# GPIOSheet.net
KiCad netlist of a schematic drawn in Altium Designer
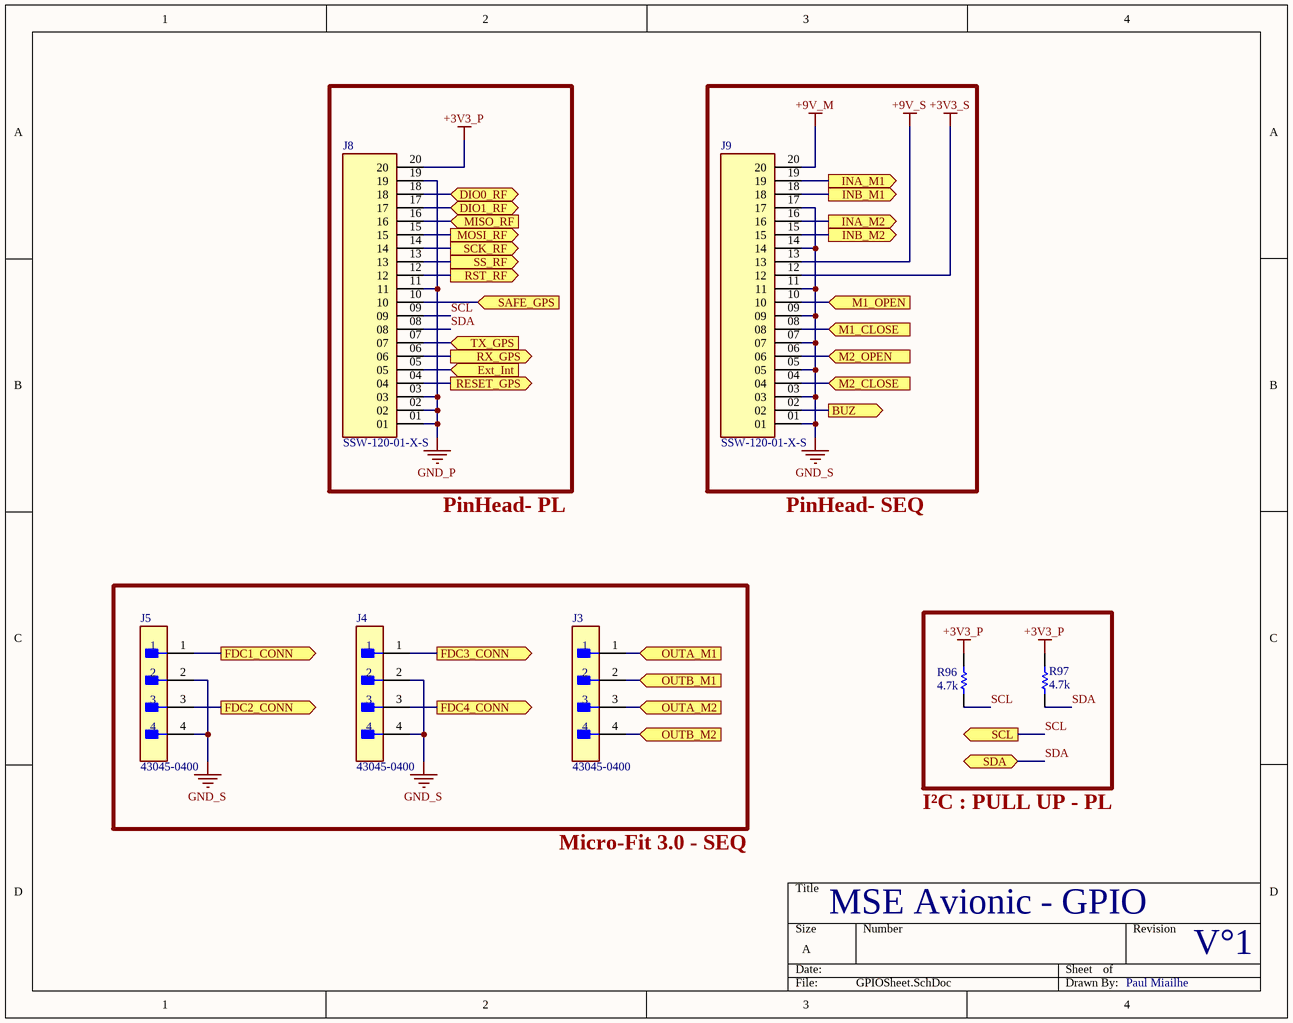
[diagram p0: GPIOSheet.SchDoc]

(export (version "E")
  (design (tool "Eeschema 10.0.6"))
  (components
    (comp (ref "J3")
      (value "43045-0400")
      (footprint "FP-43045-0400-MFG")
      (description "CONN HEADER R/A 4POS 3MM")
      (fields
        (field (name "MANUFACTURER") "Molex")
        (field (name "OCTOPART") "https://octopart.com/43045-0400-molex-287063")
      )
      (libsource (lib "Altium Content Vault") (part "c01754ab0efc13afb7424b896f394ef"))
    )
    (comp (ref "J4")
      (value "43045-0400")
      (footprint "FP-43045-0400-MFG")
      (description "CONN HEADER R/A 4POS 3MM")
      (fields
        (field (name "MANUFACTURER") "Molex")
        (field (name "OCTOPART") "https://octopart.com/43045-0400-molex-287063")
      )
      (libsource (lib "Altium Content Vault") (part "c01754ab0efc13afb7424b896f394ef"))
    )
    (comp (ref "J5")
      (value "43045-0400")
      (footprint "FP-43045-0400-MFG")
      (description "CONN HEADER R/A 4POS 3MM")
      (fields
        (field (name "MANUFACTURER") "Molex")
        (field (name "OCTOPART") "https://octopart.com/43045-0400-molex-287063")
      )
      (libsource (lib "Altium Content Vault") (part "c01754ab0efc13afb7424b896f394ef"))
    )
    (comp (ref "J8")
      (value "SSW-120-01-X-S")
      (footprint "SAMTEC_SSW-120-01-X-S")
      (description "SSW - Samtec 2.54mm Single Row Straight Socket Strip 8.5 Profile - Fast Stock")
      (fields (field (name "MP") "SSW-120-01-G-S") (field (name "MF") "Samtec"))
      (libsource (lib "Saint-Étienne School of Mines- Mines Space") (part "SSW-120-01-X-S"))
    )
    (comp (ref "J9")
      (value "SSW-120-01-X-S")
      (footprint "SAMTEC_SSW-120-01-X-S")
      (description "SSW - Samtec 2.54mm Single Row Straight Socket Strip 8.5 Profile - Fast Stock")
      (fields (field (name "MP") "SSW-120-01-G-S") (field (name "MF") "Samtec"))
      (libsource (lib "Saint-Étienne School of Mines- Mines Space") (part "SSW-120-01-X-S"))
    )
    (comp (ref "R96")
      (value "RC0603FR-074K7L")
      (footprint "RESC1608X55X25LL10T15")
      (description "Chip Resistor, 4.7 KOhm, +/- 1%, 0.1 W, -55 to 155 degC, 0603 (1608 Metric), RoHS, Tape and Reel")
      (fields
        (field (name "MANUFACTURER") "Yageo")
        (field (name "RESISTANCE") "4.7k")
        (field (name "TOLERANCE") "1%")
      )
      (libsource (lib "Altium Content Vault") (part "RES-2"))
    )
    (comp (ref "R97")
      (value "RC0603FR-074K7L")
      (footprint "RESC1608X55X25LL10T15")
      (description "Chip Resistor, 4.7 KOhm, +/- 1%, 0.1 W, -55 to 155 degC, 0603 (1608 Metric), RoHS, Tape and Reel")
      (fields
        (field (name "MANUFACTURER") "Yageo")
        (field (name "RESISTANCE") "4.7k")
        (field (name "TOLERANCE") "1%")
      )
      (libsource (lib "Altium Content Vault") (part "RES-2"))
    )
  )
  (nets
    (net (code "1") (name "+3V3_P") (class "Default")
      (node (ref "J8") (pin "20") (pinfunction "20_20") (pintype "passive"))
      (node (ref "R96") (pin "2") (pinfunction "2_2") (pintype "passive"))
      (node (ref "R97") (pin "2") (pinfunction "2_2") (pintype "passive"))
    )
    (net (code "2") (name "+3V3_S") (class "Default")
      (node (ref "J9") (pin "12") (pinfunction "12_12") (pintype "passive"))
    )
    (net (code "3") (name "+9V_M") (class "Default")
      (node (ref "J9") (pin "20") (pinfunction "20_20") (pintype "passive"))
    )
    (net (code "4") (name "+9V_S") (class "Default")
      (node (ref "J9") (pin "13") (pinfunction "13_13") (pintype "passive"))
    )
    (net (code "5") (name "/BUZ") (class "Default")
      (node (ref "J9") (pin "02") (pinfunction "02_02") (pintype "passive"))
    )
    (net (code "6") (name "/DIO0_RF") (class "Default")
      (node (ref "J8") (pin "18") (pinfunction "18_18") (pintype "passive"))
    )
    (net (code "7") (name "/DIO1_RF") (class "Default")
      (node (ref "J8") (pin "17") (pinfunction "17_17") (pintype "passive"))
    )
    (net (code "8") (name "/Ext_Int") (class "Default")
      (node (ref "J8") (pin "05") (pinfunction "05_05") (pintype "passive"))
    )
    (net (code "9") (name "/FDC1_CONN") (class "Default")
      (node (ref "J5") (pin "1") (pinfunction "1_1") (pintype "passive"))
    )
    (net (code "10") (name "/FDC2_CONN") (class "Default")
      (node (ref "J5") (pin "3") (pinfunction "3_3") (pintype "passive"))
    )
    (net (code "11") (name "/FDC3_CONN") (class "Default")
      (node (ref "J4") (pin "1") (pinfunction "1_1") (pintype "passive"))
    )
    (net (code "12") (name "/FDC4_CONN") (class "Default")
      (node (ref "J4") (pin "3") (pinfunction "3_3") (pintype "passive"))
    )
    (net (code "13") (name "/INA_M1") (class "Default")
      (node (ref "J9") (pin "19") (pinfunction "19_19") (pintype "passive"))
    )
    (net (code "14") (name "/INA_M2") (class "Default")
      (node (ref "J9") (pin "16") (pinfunction "16_16") (pintype "passive"))
    )
    (net (code "15") (name "/INB_M1") (class "Default")
      (node (ref "J9") (pin "18") (pinfunction "18_18") (pintype "passive"))
    )
    (net (code "16") (name "/INB_M2") (class "Default")
      (node (ref "J9") (pin "15") (pinfunction "15_15") (pintype "passive"))
    )
    (net (code "17") (name "/M1_CLOSE") (class "Default")
      (node (ref "J9") (pin "08") (pinfunction "08_08") (pintype "passive"))
    )
    (net (code "18") (name "/M1_OPEN") (class "Default")
      (node (ref "J9") (pin "10") (pinfunction "10_10") (pintype "passive"))
    )
    (net (code "19") (name "/M2_CLOSE") (class "Default")
      (node (ref "J9") (pin "04") (pinfunction "04_04") (pintype "passive"))
    )
    (net (code "20") (name "/M2_OPEN") (class "Default")
      (node (ref "J9") (pin "06") (pinfunction "06_06") (pintype "passive"))
    )
    (net (code "21") (name "/MISO_RF") (class "Default")
      (node (ref "J8") (pin "16") (pinfunction "16_16") (pintype "passive"))
    )
    (net (code "22") (name "/MOSI_RF") (class "Default")
      (node (ref "J8") (pin "15") (pinfunction "15_15") (pintype "passive"))
    )
    (net (code "23") (name "/OUTA_M1") (class "Default")
      (node (ref "J3") (pin "1") (pinfunction "1_1") (pintype "passive"))
    )
    (net (code "24") (name "/OUTA_M2") (class "Default")
      (node (ref "J3") (pin "3") (pinfunction "3_3") (pintype "passive"))
    )
    (net (code "25") (name "/OUTB_M1") (class "Default")
      (node (ref "J3") (pin "2") (pinfunction "2_2") (pintype "passive"))
    )
    (net (code "26") (name "/OUTB_M2") (class "Default")
      (node (ref "J3") (pin "4") (pinfunction "4_4") (pintype "passive"))
    )
    (net (code "27") (name "/RESET_GPS") (class "Default")
      (node (ref "J8") (pin "04") (pinfunction "04_04") (pintype "passive"))
    )
    (net (code "28") (name "/RST_RF") (class "Default")
      (node (ref "J8") (pin "12") (pinfunction "12_12") (pintype "passive"))
    )
    (net (code "29") (name "/RX_GPS") (class "Default")
      (node (ref "J8") (pin "06") (pinfunction "06_06") (pintype "passive"))
    )
    (net (code "30") (name "/SAFE_GPS") (class "Default")
      (node (ref "J8") (pin "10") (pinfunction "10_10") (pintype "passive"))
    )
    (net (code "31") (name "/SCK_RF") (class "Default")
      (node (ref "J8") (pin "14") (pinfunction "14_14") (pintype "passive"))
    )
    (net (code "32") (name "/SCL") (class "Default")
      (node (ref "J8") (pin "09") (pinfunction "09_09") (pintype "passive"))
      (node (ref "R96") (pin "1") (pinfunction "1_1") (pintype "passive"))
    )
    (net (code "33") (name "/SDA") (class "Default")
      (node (ref "J8") (pin "08") (pinfunction "08_08") (pintype "passive"))
      (node (ref "R97") (pin "1") (pinfunction "1_1") (pintype "passive"))
    )
    (net (code "34") (name "/SS_RF") (class "Default")
      (node (ref "J8") (pin "13") (pinfunction "13_13") (pintype "passive"))
    )
    (net (code "35") (name "/TX_GPS") (class "Default")
      (node (ref "J8") (pin "07") (pinfunction "07_07") (pintype "passive"))
    )
    (net (code "36") (name "GND_P") (class "Default")
      (node (ref "J8") (pin "01") (pinfunction "01_01") (pintype "passive"))
      (node (ref "J8") (pin "02") (pinfunction "02_02") (pintype "passive"))
      (node (ref "J8") (pin "03") (pinfunction "03_03") (pintype "passive"))
      (node (ref "J8") (pin "11") (pinfunction "11_11") (pintype "passive"))
      (node (ref "J8") (pin "19") (pinfunction "19_19") (pintype "passive"))
    )
    (net (code "37") (name "GND_S") (class "Default")
      (node (ref "J4") (pin "2") (pinfunction "2_2") (pintype "passive"))
      (node (ref "J4") (pin "4") (pinfunction "4_4") (pintype "passive"))
      (node (ref "J5") (pin "2") (pinfunction "2_2") (pintype "passive"))
      (node (ref "J5") (pin "4") (pinfunction "4_4") (pintype "passive"))
      (node (ref "J9") (pin "01") (pinfunction "01_01") (pintype "passive"))
      (node (ref "J9") (pin "03") (pinfunction "03_03") (pintype "passive"))
      (node (ref "J9") (pin "05") (pinfunction "05_05") (pintype "passive"))
      (node (ref "J9") (pin "07") (pinfunction "07_07") (pintype "passive"))
      (node (ref "J9") (pin "09") (pinfunction "09_09") (pintype "passive"))
      (node (ref "J9") (pin "11") (pinfunction "11_11") (pintype "passive"))
      (node (ref "J9") (pin "14") (pinfunction "14_14") (pintype "passive"))
      (node (ref "J9") (pin "17") (pinfunction "17_17") (pintype "passive"))
    )
  )
)
